# PRY237_-_Laser_Rec.net
KiCad netlist of a schematic drawn in EAGLE
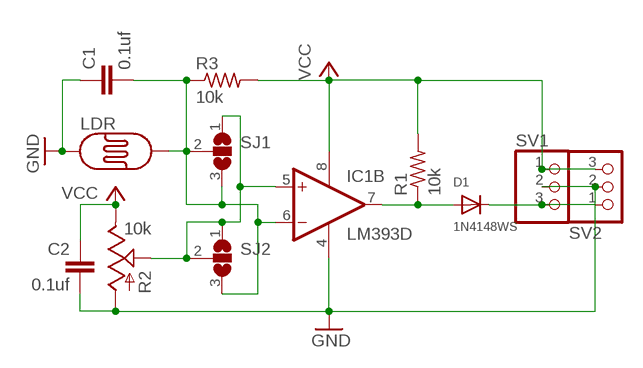
[diagram p0: schematic, sheet 1]

(export (version "E")
  (design (tool "Eeschema 10.0.6"))
  (components
    (comp (ref "C1")
      (value "0.1uf")
      (footprint "eagle-import:C0805")
      (libsource (lib "eagle-import") (part "C-EUC0805"))
    )
    (comp (ref "C2")
      (value "0.1uf")
      (footprint "eagle-import:C0805")
      (libsource (lib "eagle-import") (part "C-EUC0805"))
    )
    (comp (ref "D1")
      (value "1N4148WS")
      (footprint "eagle-import:SOD-323F")
      (libsource (lib "eagle-import") (part "DIODESOD-323F"))
    )
    (comp (ref "IC1")
      (value "LM393D")
      (footprint "eagle-import:SO08")
      (libsource (lib "eagle-import") (part "LM393D"))
    )
    (comp (ref "LDR")
      (value "PHOTOCELLPTH")
      (footprint "eagle-import:PHOTOCELL")
      (libsource (lib "eagle-import") (part "PHOTOCELLPTH"))
    )
    (comp (ref "R1")
      (value "10k")
      (footprint "eagle-import:M0805")
      (libsource (lib "eagle-import") (part "R-US_M0805"))
    )
    (comp (ref "R2")
      (value "10k")
      (footprint "eagle-import:CT6")
      (libsource (lib "eagle-import") (part "TRIM_US-CT6"))
    )
    (comp (ref "R3")
      (value "10k")
      (footprint "eagle-import:M0805")
      (libsource (lib "eagle-import") (part "R-US_M0805"))
    )
    (comp (ref "SJ1")
      (value "SJ2W")
      (footprint "eagle-import:SJ_2")
      (libsource (lib "eagle-import") (part "SJ2W"))
    )
    (comp (ref "SJ2")
      (value "SJ2W")
      (footprint "eagle-import:SJ_2")
      (libsource (lib "eagle-import") (part "SJ2W"))
    )
    (comp (ref "SV1")
      (value "PINHD-1X3")
      (footprint "eagle-import:1X03")
      (libsource (lib "eagle-import") (part "PINHD-1X3"))
    )
    (comp (ref "SV2")
      (value "PINHD-1X3")
      (footprint "eagle-import:1X03")
      (libsource (lib "eagle-import") (part "PINHD-1X3"))
    )
  )
  (nets
    (net (code "1") (name "GND") (class "Default")
      (node (ref "C1") (pin "1") (pinfunction "1_1") (pintype "passive"))
      (node (ref "C2") (pin "2") (pinfunction "2_2") (pintype "passive"))
      (node (ref "IC1") (pin "4") (pinfunction "V-_4") (pintype "power_in"))
      (node (ref "LDR") (pin "1") (pinfunction "P$1_1") (pintype "bidirectional"))
      (node (ref "R2") (pin "A") (pinfunction "A_A") (pintype "passive"))
      (node (ref "SV1") (pin "2") (pinfunction "2_2") (pintype "passive"))
      (node (ref "SV2") (pin "2") (pinfunction "2_2") (pintype "passive"))
    )
    (net (code "2") (name "Net-(D1-PadC)") (class "Default")
      (node (ref "D1") (pin "C") (pinfunction "C_C") (pintype "passive"))
      (node (ref "SV1") (pin "3") (pinfunction "3_3") (pintype "passive"))
      (node (ref "SV2") (pin "1") (pinfunction "1_1") (pintype "passive"))
    )
    (net (code "3") (name "Net-(IC1B-+IN)") (class "Default")
      (node (ref "IC1") (pin "5") (pinfunction "+IN_5") (pintype "input"))
      (node (ref "R2") (pin "S") (pinfunction "S_S") (pintype "passive"))
      (node (ref "SJ1") (pin "1") (pinfunction "1_1") (pintype "passive"))
      (node (ref "SJ2") (pin "1") (pinfunction "1_1") (pintype "passive"))
      (node (ref "SJ2") (pin "2") (pinfunction "2_2") (pintype "passive"))
    )
    (net (code "4") (name "Net-(IC1B--IN)") (class "Default")
      (node (ref "C1") (pin "2") (pinfunction "2_2") (pintype "passive"))
      (node (ref "IC1") (pin "6") (pinfunction "-IN_6") (pintype "input"))
      (node (ref "LDR") (pin "2") (pinfunction "P$2_2") (pintype "bidirectional"))
      (node (ref "R3") (pin "1") (pinfunction "1_1") (pintype "passive"))
      (node (ref "SJ1") (pin "2") (pinfunction "2_2") (pintype "passive"))
      (node (ref "SJ1") (pin "3") (pinfunction "3_3") (pintype "passive"))
      (node (ref "SJ2") (pin "3") (pinfunction "3_3") (pintype "passive"))
    )
    (net (code "5") (name "Net-(IC1B-OUT)") (class "Default")
      (node (ref "D1") (pin "A") (pinfunction "A_A") (pintype "passive"))
      (node (ref "IC1") (pin "7") (pinfunction "OUT_7") (pintype "output"))
      (node (ref "R1") (pin "1") (pinfunction "1_1") (pintype "passive"))
    )
    (net (code "6") (name "VCC") (class "Default")
      (node (ref "C2") (pin "1") (pinfunction "1_1") (pintype "passive"))
      (node (ref "IC1") (pin "8") (pinfunction "V+_8") (pintype "power_in"))
      (node (ref "R1") (pin "2") (pinfunction "2_2") (pintype "passive"))
      (node (ref "R2") (pin "E") (pinfunction "E_E") (pintype "passive"))
      (node (ref "R3") (pin "2") (pinfunction "2_2") (pintype "passive"))
      (node (ref "SV1") (pin "1") (pinfunction "1_1") (pintype "passive"))
      (node (ref "SV2") (pin "3") (pinfunction "3_3") (pintype "passive"))
    )
  )
)
